# BMS_Master_V2_0.net
KiCad netlist of a schematic drawn in EAGLE
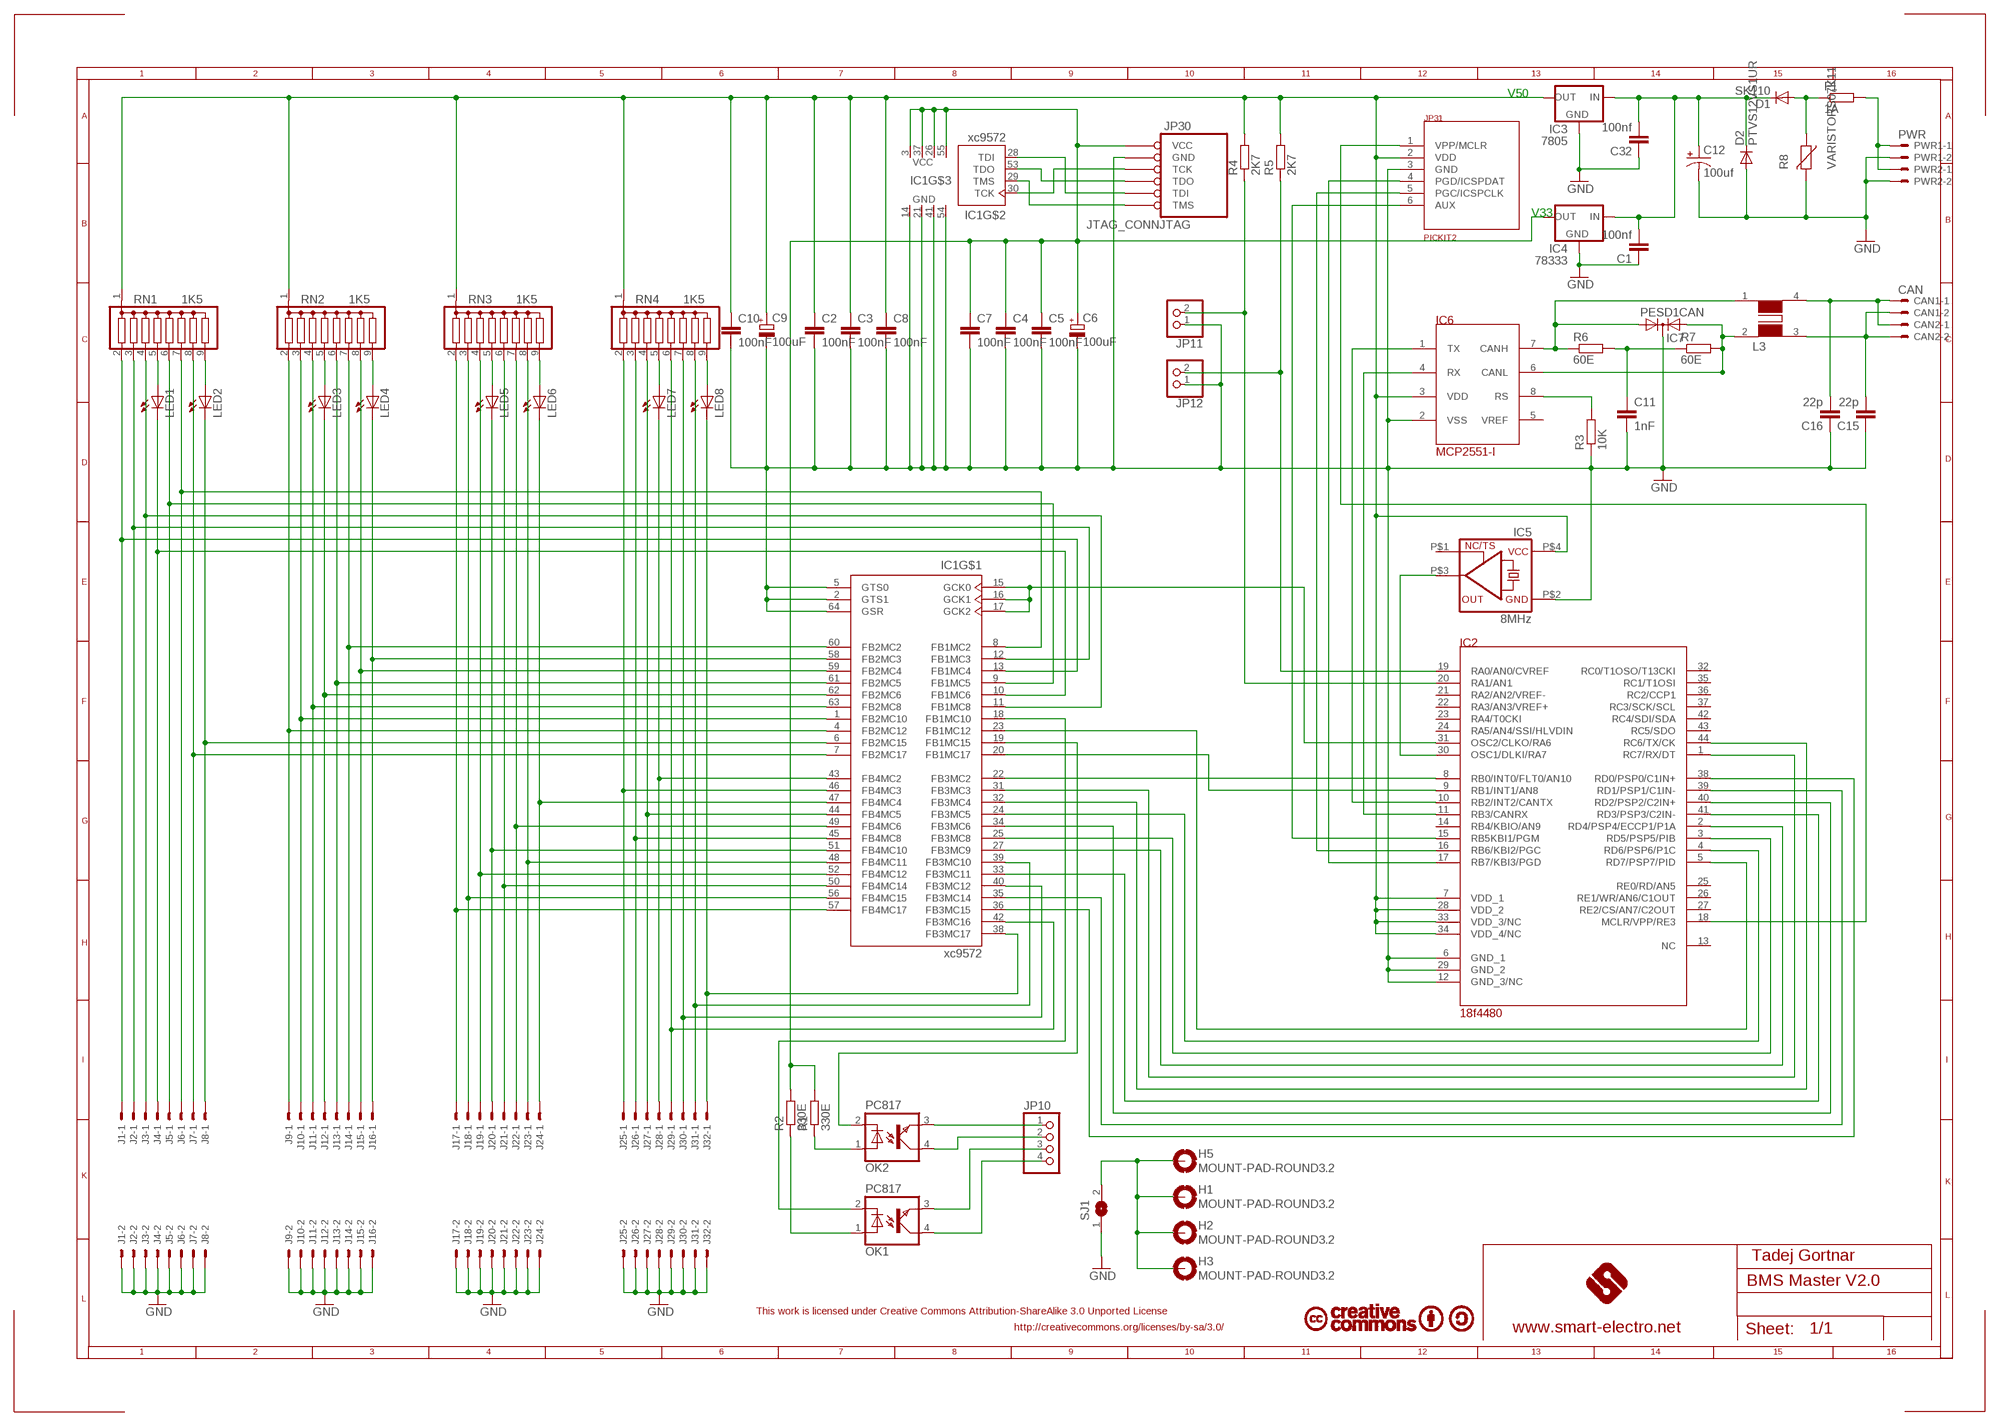
[diagram p0: schematic, sheet 1]

(export (version "E")
  (design (tool "Eeschema 10.0.6"))
  (components
    (comp (ref "C1")
      (value "100nf")
      (footprint "eagle-import:C0805")
      (libsource (lib "eagle-import") (part "resistor_C-EUC0805"))
    )
    (comp (ref "C2")
      (value "100nF")
      (footprint "eagle-import:C0805")
      (libsource (lib "eagle-import") (part "C-EUC0805"))
    )
    (comp (ref "C3")
      (value "100nF")
      (footprint "eagle-import:C0805")
      (libsource (lib "eagle-import") (part "C-EUC0805"))
    )
    (comp (ref "C4")
      (value "100nF")
      (footprint "eagle-import:C0805")
      (libsource (lib "eagle-import") (part "C-EUC0805"))
    )
    (comp (ref "C5")
      (value "100nF")
      (footprint "eagle-import:C0805")
      (libsource (lib "eagle-import") (part "C-EUC0805"))
    )
    (comp (ref "C6")
      (value "100uF")
      (footprint "eagle-import:E2,5-5")
      (libsource (lib "eagle-import") (part "CPOL-EUE2.5-5"))
    )
    (comp (ref "C7")
      (value "100nF")
      (footprint "eagle-import:C0805")
      (libsource (lib "eagle-import") (part "C-EUC0805"))
    )
    (comp (ref "C8")
      (value "100nF")
      (footprint "eagle-import:C0805")
      (libsource (lib "eagle-import") (part "C-EUC0805"))
    )
    (comp (ref "C9")
      (value "100uF")
      (footprint "eagle-import:E2,5-5")
      (libsource (lib "eagle-import") (part "CPOL-EUE2.5-5"))
    )
    (comp (ref "C10")
      (value "100nF")
      (footprint "eagle-import:C0805")
      (libsource (lib "eagle-import") (part "C-EUC0805"))
    )
    (comp (ref "C11")
      (value "1nF")
      (footprint "eagle-import:C0805")
      (libsource (lib "eagle-import") (part "C-EUC0805"))
    )
    (comp (ref "C12")
      (value "100uf")
      (footprint "eagle-import:PANASONIC_C")
      (libsource (lib "eagle-import") (part "CPOL-USC"))
    )
    (comp (ref "C15")
      (value "22p")
      (footprint "eagle-import:C0805")
      (libsource (lib "eagle-import") (part "C-EUC0805"))
    )
    (comp (ref "C16")
      (value "22p")
      (footprint "eagle-import:C0805")
      (libsource (lib "eagle-import") (part "C-EUC0805"))
    )
    (comp (ref "C32")
      (value "100nf")
      (footprint "eagle-import:C0805")
      (libsource (lib "eagle-import") (part "resistor_C-EUC0805"))
    )
    (comp (ref "CAN1")
      (value "CAN")
      (footprint "eagle-import:6410-02")
      (libsource (lib "eagle-import") (part "22-?-0227-2021"))
    )
    (comp (ref "CAN2")
      (value "CAN")
      (footprint "eagle-import:6410-02")
      (libsource (lib "eagle-import") (part "22-?-0227-2021"))
    )
    (comp (ref "D1")
      (value "SK110")
      (footprint "eagle-import:MINIMELF")
      (libsource (lib "eagle-import") (part "DIODE-MINIMELF"))
    )
    (comp (ref "D2")
      (value "PTVS12VS1UR")
      (footprint "eagle-import:SOD323-W")
      (libsource (lib "eagle-import") (part "DIODE-SOD323-W"))
    )
    (comp (ref "F1")
      (value "1A")
      (footprint "eagle-import:R1206")
      (libsource (lib "eagle-import") (part "resistor_R-EU_R1206"))
    )
    (comp (ref "H1")
      (value "MOUNT-PAD-ROUND3.2")
      (footprint "eagle-import:3,2-PAD")
      (libsource (lib "eagle-import") (part "MOUNT-PAD-ROUND3.2"))
    )
    (comp (ref "H2")
      (value "MOUNT-PAD-ROUND3.2")
      (footprint "eagle-import:3,2-PAD")
      (libsource (lib "eagle-import") (part "MOUNT-PAD-ROUND3.2"))
    )
    (comp (ref "H3")
      (value "MOUNT-PAD-ROUND3.2")
      (footprint "eagle-import:3,2-PAD")
      (libsource (lib "eagle-import") (part "MOUNT-PAD-ROUND3.2"))
    )
    (comp (ref "H5")
      (value "MOUNT-PAD-ROUND3.2")
      (footprint "eagle-import:3,2-PAD")
      (libsource (lib "eagle-import") (part "MOUNT-PAD-ROUND3.2"))
    )
    (comp (ref "IC1")
      (value "xc9572")
      (footprint "eagle-import:VQ64")
      (libsource (lib "eagle-import") (part "XC9572-VQ64"))
    )
    (comp (ref "IC2")
      (value "18f4480")
      (footprint "eagle-import:TQFP44")
      (libsource (lib "eagle-import") (part "PIC18F4804"))
    )
    (comp (ref "IC3")
      (value "7805")
      (footprint "eagle-import:SOT223")
      (libsource (lib "eagle-import") (part "78XXS'SOT223'"))
    )
    (comp (ref "IC4")
      (value "78333")
      (footprint "eagle-import:SOT223")
      (libsource (lib "eagle-import") (part "78XXS'SOT223'"))
    )
    (comp (ref "IC5")
      (value "8MHz")
      (footprint "eagle-import:CSX750")
      (libsource (lib "eagle-import") (part "OSCI7X5"))
    )
    (comp (ref "IC6")
      (value "MCP2551-I")
      (footprint "eagle-import:SO-08")
      (libsource (lib "eagle-import") (part "MCP2551"))
    )
    (comp (ref "IC7")
      (value "PESD1CAN")
      (footprint "eagle-import:SOT23")
      (libsource (lib "eagle-import") (part "BAS70-06"))
    )
    (comp (ref "J1")
      (value "22-27-2021-02")
      (footprint "eagle-import:6410-02")
      (libsource (lib "eagle-import") (part "22-?-0227-2021"))
    )
    (comp (ref "J2")
      (value "22-27-2021-02")
      (footprint "eagle-import:6410-02")
      (libsource (lib "eagle-import") (part "22-?-0227-2021"))
    )
    (comp (ref "J3")
      (value "22-27-2021-02")
      (footprint "eagle-import:6410-02")
      (libsource (lib "eagle-import") (part "22-?-0227-2021"))
    )
    (comp (ref "J4")
      (value "22-27-2021-02")
      (footprint "eagle-import:6410-02")
      (libsource (lib "eagle-import") (part "22-?-0227-2021"))
    )
    (comp (ref "J5")
      (value "22-27-2021-02")
      (footprint "eagle-import:6410-02")
      (libsource (lib "eagle-import") (part "22-?-0227-2021"))
    )
    (comp (ref "J6")
      (value "22-27-2021-02")
      (footprint "eagle-import:6410-02")
      (libsource (lib "eagle-import") (part "22-?-0227-2021"))
    )
    (comp (ref "J7")
      (value "22-27-2021-02")
      (footprint "eagle-import:6410-02")
      (libsource (lib "eagle-import") (part "22-?-0227-2021"))
    )
    (comp (ref "J8")
      (value "22-27-2021-02")
      (footprint "eagle-import:6410-02")
      (libsource (lib "eagle-import") (part "22-?-0227-2021"))
    )
    (comp (ref "J9")
      (value "22-27-2021-02")
      (footprint "eagle-import:6410-02")
      (libsource (lib "eagle-import") (part "22-?-0227-2021"))
    )
    (comp (ref "J10")
      (value "22-27-2021-02")
      (footprint "eagle-import:6410-02")
      (libsource (lib "eagle-import") (part "22-?-0227-2021"))
    )
    (comp (ref "J11")
      (value "22-27-2021-02")
      (footprint "eagle-import:6410-02")
      (libsource (lib "eagle-import") (part "22-?-0227-2021"))
    )
    (comp (ref "J12")
      (value "22-27-2021-02")
      (footprint "eagle-import:6410-02")
      (libsource (lib "eagle-import") (part "22-?-0227-2021"))
    )
    (comp (ref "J13")
      (value "22-27-2021-02")
      (footprint "eagle-import:6410-02")
      (libsource (lib "eagle-import") (part "22-?-0227-2021"))
    )
    (comp (ref "J14")
      (value "22-27-2021-02")
      (footprint "eagle-import:6410-02")
      (libsource (lib "eagle-import") (part "22-?-0227-2021"))
    )
    (comp (ref "J15")
      (value "22-27-2021-02")
      (footprint "eagle-import:6410-02")
      (libsource (lib "eagle-import") (part "22-?-0227-2021"))
    )
    (comp (ref "J16")
      (value "22-27-2021-02")
      (footprint "eagle-import:6410-02")
      (libsource (lib "eagle-import") (part "22-?-0227-2021"))
    )
    (comp (ref "J17")
      (value "22-27-2021-02")
      (footprint "eagle-import:6410-02")
      (libsource (lib "eagle-import") (part "22-?-0227-2021"))
    )
    (comp (ref "J18")
      (value "22-27-2021-02")
      (footprint "eagle-import:6410-02")
      (libsource (lib "eagle-import") (part "22-?-0227-2021"))
    )
    (comp (ref "J19")
      (value "22-27-2021-02")
      (footprint "eagle-import:6410-02")
      (libsource (lib "eagle-import") (part "22-?-0227-2021"))
    )
    (comp (ref "J20")
      (value "22-27-2021-02")
      (footprint "eagle-import:6410-02")
      (libsource (lib "eagle-import") (part "22-?-0227-2021"))
    )
    (comp (ref "J21")
      (value "22-27-2021-02")
      (footprint "eagle-import:6410-02")
      (libsource (lib "eagle-import") (part "22-?-0227-2021"))
    )
    (comp (ref "J22")
      (value "22-27-2021-02")
      (footprint "eagle-import:6410-02")
      (libsource (lib "eagle-import") (part "22-?-0227-2021"))
    )
    (comp (ref "J23")
      (value "22-27-2021-02")
      (footprint "eagle-import:6410-02")
      (libsource (lib "eagle-import") (part "22-?-0227-2021"))
    )
    (comp (ref "J24")
      (value "22-27-2021-02")
      (footprint "eagle-import:6410-02")
      (libsource (lib "eagle-import") (part "22-?-0227-2021"))
    )
    (comp (ref "J25")
      (value "22-27-2021-02")
      (footprint "eagle-import:6410-02")
      (libsource (lib "eagle-import") (part "22-?-0227-2021"))
    )
    (comp (ref "J26")
      (value "22-27-2021-02")
      (footprint "eagle-import:6410-02")
      (libsource (lib "eagle-import") (part "22-?-0227-2021"))
    )
    (comp (ref "J27")
      (value "22-27-2021-02")
      (footprint "eagle-import:6410-02")
      (libsource (lib "eagle-import") (part "22-?-0227-2021"))
    )
    (comp (ref "J28")
      (value "22-27-2021-02")
      (footprint "eagle-import:6410-02")
      (libsource (lib "eagle-import") (part "22-?-0227-2021"))
    )
    (comp (ref "J29")
      (value "22-27-2021-02")
      (footprint "eagle-import:6410-02")
      (libsource (lib "eagle-import") (part "22-?-0227-2021"))
    )
    (comp (ref "J30")
      (value "22-27-2021-02")
      (footprint "eagle-import:6410-02")
      (libsource (lib "eagle-import") (part "22-?-0227-2021"))
    )
    (comp (ref "J31")
      (value "22-27-2021-02")
      (footprint "eagle-import:6410-02")
      (libsource (lib "eagle-import") (part "22-?-0227-2021"))
    )
    (comp (ref "J32")
      (value "22-27-2021-02")
      (footprint "eagle-import:6410-02")
      (libsource (lib "eagle-import") (part "22-?-0227-2021"))
    )
    (comp (ref "JP10")
      (value "PINHD-1X4")
      (footprint "eagle-import:1X04")
      (libsource (lib "eagle-import") (part "PINHD-1X4"))
    )
    (comp (ref "JP11")
      (value "PINHD-1X2")
      (footprint "eagle-import:1X02")
      (libsource (lib "eagle-import") (part "PINHD-1X2"))
    )
    (comp (ref "JP12")
      (value "PINHD-1X2")
      (footprint "eagle-import:1X02")
      (libsource (lib "eagle-import") (part "PINHD-1X2"))
    )
    (comp (ref "JP30")
      (value "JTAG_CONNJTAG")
      (footprint "eagle-import:PIN06")
      (libsource (lib "eagle-import") (part "JTAG_CONNJTAG"))
    )
    (comp (ref "JP31")
      (value "PICKIT2")
      (footprint "eagle-import:PINHD-1X6")
      (libsource (lib "eagle-import") (part "PICKIT2"))
    )
    (comp (ref "L3")
      (value "WE-DD_M/S")
      (footprint "eagle-import:WE-DD_M_S")
      (libsource (lib "eagle-import") (part "WE-DD_M/S"))
    )
    (comp (ref "LED1")
      (value "LEDCHIPLED_0805")
      (footprint "eagle-import:CHIPLED_0805")
      (libsource (lib "eagle-import") (part "LEDCHIPLED_0805"))
    )
    (comp (ref "LED2")
      (value "LEDCHIPLED_0805")
      (footprint "eagle-import:CHIPLED_0805")
      (libsource (lib "eagle-import") (part "LEDCHIPLED_0805"))
    )
    (comp (ref "LED3")
      (value "LEDCHIPLED_0805")
      (footprint "eagle-import:CHIPLED_0805")
      (libsource (lib "eagle-import") (part "LEDCHIPLED_0805"))
    )
    (comp (ref "LED4")
      (value "LEDCHIPLED_0805")
      (footprint "eagle-import:CHIPLED_0805")
      (libsource (lib "eagle-import") (part "LEDCHIPLED_0805"))
    )
    (comp (ref "LED5")
      (value "LEDCHIPLED_0805")
      (footprint "eagle-import:CHIPLED_0805")
      (libsource (lib "eagle-import") (part "LEDCHIPLED_0805"))
    )
    (comp (ref "LED6")
      (value "LEDCHIPLED_0805")
      (footprint "eagle-import:CHIPLED_0805")
      (libsource (lib "eagle-import") (part "LEDCHIPLED_0805"))
    )
    (comp (ref "LED7")
      (value "LEDCHIPLED_0805")
      (footprint "eagle-import:CHIPLED_0805")
      (libsource (lib "eagle-import") (part "LEDCHIPLED_0805"))
    )
    (comp (ref "LED8")
      (value "LEDCHIPLED_0805")
      (footprint "eagle-import:CHIPLED_0805")
      (libsource (lib "eagle-import") (part "LEDCHIPLED_0805"))
    )
    (comp (ref "OK1")
      (value "PC817")
      (footprint "eagle-import:DIL04")
      (libsource (lib "eagle-import") (part "PC817"))
    )
    (comp (ref "OK2")
      (value "PC817")
      (footprint "eagle-import:DIL04")
      (libsource (lib "eagle-import") (part "PC817"))
    )
    (comp (ref "PWR1")
      (value "PWR")
      (footprint "eagle-import:6410-02")
      (libsource (lib "eagle-import") (part "22-?-0227-2021"))
    )
    (comp (ref "PWR2")
      (value "PWR")
      (footprint "eagle-import:6410-02")
      (libsource (lib "eagle-import") (part "22-?-0227-2021"))
    )
    (comp (ref "R1")
      (value "330E")
      (footprint "eagle-import:M0805")
      (libsource (lib "eagle-import") (part "R-EU_M0805"))
    )
    (comp (ref "R2")
      (value "330E")
      (footprint "eagle-import:M0805")
      (libsource (lib "eagle-import") (part "R-EU_M0805"))
    )
    (comp (ref "R3")
      (value "10K")
      (footprint "eagle-import:M0805")
      (libsource (lib "eagle-import") (part "R-EU_M0805"))
    )
    (comp (ref "R4")
      (value "2K7")
      (footprint "eagle-import:M0805")
      (libsource (lib "eagle-import") (part "R-EU_M0805"))
    )
    (comp (ref "R5")
      (value "2K7")
      (footprint "eagle-import:M0805")
      (libsource (lib "eagle-import") (part "R-EU_M0805"))
    )
    (comp (ref "R6")
      (value "60E")
      (footprint "eagle-import:R0805")
      (libsource (lib "eagle-import") (part "R-EU_R0805"))
    )
    (comp (ref "R7")
      (value "60E")
      (footprint "eagle-import:R0805")
      (libsource (lib "eagle-import") (part "R-EU_R0805"))
    )
    (comp (ref "R8")
      (value "VARISTORS07K11")
      (footprint "eagle-import:S07K11")
      (libsource (lib "eagle-import") (part "VARISTORS07K11"))
    )
    (comp (ref "RN1")
      (value "1K5")
      (footprint "eagle-import:SIL9")
      (libsource (lib "eagle-import") (part "G08R"))
    )
    (comp (ref "RN2")
      (value "1K5")
      (footprint "eagle-import:SIL9")
      (libsource (lib "eagle-import") (part "G08R"))
    )
    (comp (ref "RN3")
      (value "1K5")
      (footprint "eagle-import:SIL9")
      (libsource (lib "eagle-import") (part "G08R"))
    )
    (comp (ref "RN4")
      (value "1K5")
      (footprint "eagle-import:SIL9")
      (libsource (lib "eagle-import") (part "G08R"))
    )
    (comp (ref "SJ1") (value "SJ") (footprint "eagle-import:SJ") (libsource (lib "eagle-import") (part "SJ")))
  )
  (nets
    (net (code "1") (name "/V33") (class "Default")
      (node (ref "C4") (pin "1") (pinfunction "1_1") (pintype "passive"))
      (node (ref "C5") (pin "1") (pinfunction "1_1") (pintype "passive"))
      (node (ref "C6") (pin "+") (pinfunction "+_+") (pintype "passive"))
      (node (ref "C7") (pin "1") (pinfunction "1_1") (pintype "passive"))
      (node (ref "IC1") (pin "26") (pinfunction "VCC_26") (pintype "power_in"))
      (node (ref "IC1") (pin "3") (pinfunction "VCC_3") (pintype "power_in"))
      (node (ref "IC1") (pin "37") (pinfunction "VCC_37") (pintype "power_in"))
      (node (ref "IC1") (pin "55") (pinfunction "VCC_55") (pintype "power_in"))
      (node (ref "IC4") (pin "3") (pinfunction "OUT_3") (pintype "passive"))
      (node (ref "JP30") (pin "1") (pinfunction "VCC_1") (pintype "passive"))
      (node (ref "R1") (pin "2") (pinfunction "2_2") (pintype "passive"))
      (node (ref "R2") (pin "2") (pinfunction "2_2") (pintype "passive"))
    )
    (net (code "2") (name "/V50") (class "Default")
      (node (ref "C10") (pin "1") (pinfunction "1_1") (pintype "passive"))
      (node (ref "C2") (pin "1") (pinfunction "1_1") (pintype "passive"))
      (node (ref "C3") (pin "1") (pinfunction "1_1") (pintype "passive"))
      (node (ref "C8") (pin "1") (pinfunction "1_1") (pintype "passive"))
      (node (ref "C9") (pin "+") (pinfunction "+_+") (pintype "passive"))
      (node (ref "IC2") (pin "28") (pinfunction "VDD_2_28") (pintype "power_in"))
      (node (ref "IC2") (pin "33") (pinfunction "VDD_3/NC_33") (pintype "power_in"))
      (node (ref "IC2") (pin "34") (pinfunction "VDD_4/NC_34") (pintype "power_in"))
      (node (ref "IC2") (pin "7") (pinfunction "VDD_1_7") (pintype "power_in"))
      (node (ref "IC3") (pin "3") (pinfunction "OUT_3") (pintype "passive"))
      (node (ref "IC5") (pin "P$4") (pinfunction "VCC_P$4") (pintype "power_in"))
      (node (ref "IC6") (pin "3") (pinfunction "VDD_3") (pintype "power_in"))
      (node (ref "JP31") (pin "2") (pinfunction "VDD_2") (pintype "bidirectional"))
      (node (ref "R4") (pin "2") (pinfunction "2_2") (pintype "passive"))
      (node (ref "R5") (pin "2") (pinfunction "2_2") (pintype "passive"))
      (node (ref "RN1") (pin "1") (pinfunction "1_1") (pintype "passive"))
      (node (ref "RN2") (pin "1") (pinfunction "1_1") (pintype "passive"))
      (node (ref "RN3") (pin "1") (pinfunction "1_1") (pintype "passive"))
      (node (ref "RN4") (pin "1") (pinfunction "1_1") (pintype "passive"))
    )
    (net (code "3") (name "GND") (class "Default")
      (node (ref "C1") (pin "1") (pinfunction "1_1") (pintype "passive"))
      (node (ref "C10") (pin "2") (pinfunction "2_2") (pintype "passive"))
      (node (ref "C11") (pin "2") (pinfunction "2_2") (pintype "passive"))
      (node (ref "C12") (pin "-") (pinfunction "-_-") (pintype "passive"))
      (node (ref "C15") (pin "1") (pinfunction "1_1") (pintype "passive"))
      (node (ref "C16") (pin "1") (pinfunction "1_1") (pintype "passive"))
      (node (ref "C2") (pin "2") (pinfunction "2_2") (pintype "passive"))
      (node (ref "C3") (pin "2") (pinfunction "2_2") (pintype "passive"))
      (node (ref "C32") (pin "1") (pinfunction "1_1") (pintype "passive"))
      (node (ref "C4") (pin "2") (pinfunction "2_2") (pintype "passive"))
      (node (ref "C5") (pin "2") (pinfunction "2_2") (pintype "passive"))
      (node (ref "C6") (pin "-") (pinfunction "-_-") (pintype "passive"))
      (node (ref "C7") (pin "2") (pinfunction "2_2") (pintype "passive"))
      (node (ref "C8") (pin "2") (pinfunction "2_2") (pintype "passive"))
      (node (ref "C9") (pin "-") (pinfunction "-_-") (pintype "passive"))
      (node (ref "D2") (pin "A") (pinfunction "A_A") (pintype "passive"))
      (node (ref "IC1") (pin "14") (pinfunction "GND_14") (pintype "power_in"))
      (node (ref "IC1") (pin "2") (pinfunction "GTS1_2") (pintype "input"))
      (node (ref "IC1") (pin "21") (pinfunction "GND_21") (pintype "power_in"))
      (node (ref "IC1") (pin "41") (pinfunction "GND_41") (pintype "power_in"))
      (node (ref "IC1") (pin "5") (pinfunction "GTS0_5") (pintype "input"))
      (node (ref "IC1") (pin "54") (pinfunction "GND_54") (pintype "power_in"))
      (node (ref "IC1") (pin "64") (pinfunction "GSR_64") (pintype "input"))
      (node (ref "IC2") (pin "12") (pinfunction "GND_3/NC_12") (pintype "power_in"))
      (node (ref "IC2") (pin "29") (pinfunction "GND_2_29") (pintype "power_in"))
      (node (ref "IC2") (pin "6") (pinfunction "GND_1_6") (pintype "power_in"))
      (node (ref "IC3") (pin "2") (pinfunction "GND_2") (pintype "input"))
      (node (ref "IC4") (pin "2") (pinfunction "GND_2") (pintype "input"))
      (node (ref "IC5") (pin "P$2") (pinfunction "GND_P$2") (pintype "power_in"))
      (node (ref "IC6") (pin "2") (pinfunction "VSS_2") (pintype "power_in"))
      (node (ref "IC7") (pin "3") (pinfunction "C_3") (pintype "passive"))
      (node (ref "J1") (pin "2") (pinfunction "S_2") (pintype "passive"))
      (node (ref "J10") (pin "2") (pinfunction "S_2") (pintype "passive"))
      (node (ref "J11") (pin "2") (pinfunction "S_2") (pintype "passive"))
      (node (ref "J12") (pin "2") (pinfunction "S_2") (pintype "passive"))
      (node (ref "J13") (pin "2") (pinfunction "S_2") (pintype "passive"))
      (node (ref "J14") (pin "2") (pinfunction "S_2") (pintype "passive"))
      (node (ref "J15") (pin "2") (pinfunction "S_2") (pintype "passive"))
      (node (ref "J16") (pin "2") (pinfunction "S_2") (pintype "passive"))
      (node (ref "J17") (pin "2") (pinfunction "S_2") (pintype "passive"))
      (node (ref "J18") (pin "2") (pinfunction "S_2") (pintype "passive"))
      (node (ref "J19") (pin "2") (pinfunction "S_2") (pintype "passive"))
      (node (ref "J2") (pin "2") (pinfunction "S_2") (pintype "passive"))
      (node (ref "J20") (pin "2") (pinfunction "S_2") (pintype "passive"))
      (node (ref "J21") (pin "2") (pinfunction "S_2") (pintype "passive"))
      (node (ref "J22") (pin "2") (pinfunction "S_2") (pintype "passive"))
      (node (ref "J23") (pin "2") (pinfunction "S_2") (pintype "passive"))
      (node (ref "J24") (pin "2") (pinfunction "S_2") (pintype "passive"))
      (node (ref "J25") (pin "2") (pinfunction "S_2") (pintype "passive"))
      (node (ref "J26") (pin "2") (pinfunction "S_2") (pintype "passive"))
      (node (ref "J27") (pin "2") (pinfunction "S_2") (pintype "passive"))
      (node (ref "J28") (pin "2") (pinfunction "S_2") (pintype "passive"))
      (node (ref "J29") (pin "2") (pinfunction "S_2") (pintype "passive"))
      (node (ref "J3") (pin "2") (pinfunction "S_2") (pintype "passive"))
      (node (ref "J30") (pin "2") (pinfunction "S_2") (pintype "passive"))
      (node (ref "J31") (pin "2") (pinfunction "S_2") (pintype "passive"))
      (node (ref "J32") (pin "2") (pinfunction "S_2") (pintype "passive"))
      (node (ref "J4") (pin "2") (pinfunction "S_2") (pintype "passive"))
      (node (ref "J5") (pin "2") (pinfunction "S_2") (pintype "passive"))
      (node (ref "J6") (pin "2") (pinfunction "S_2") (pintype "passive"))
      (node (ref "J7") (pin "2") (pinfunction "S_2") (pintype "passive"))
      (node (ref "J8") (pin "2") (pinfunction "S_2") (pintype "passive"))
      (node (ref "J9") (pin "2") (pinfunction "S_2") (pintype "passive"))
      (node (ref "JP11") (pin "1") (pinfunction "1_1") (pintype "passive"))
      (node (ref "JP12") (pin "1") (pinfunction "1_1") (pintype "passive"))
      (node (ref "JP30") (pin "2") (pinfunction "GND_2") (pintype "passive"))
      (node (ref "JP31") (pin "3") (pinfunction "GND_3") (pintype "bidirectional"))
      (node (ref "PWR1") (pin "2") (pinfunction "S_2") (pintype "passive"))
      (node (ref "PWR2") (pin "2") (pinfunction "S_2") (pintype "passive"))
      (node (ref "R3") (pin "1") (pinfunction "1_1") (pintype "passive"))
      (node (ref "R8") (pin "2") (pinfunction "2_2") (pintype "passive"))
      (node (ref "SJ1") (pin "1") (pinfunction "1_1") (pintype "passive"))
    )
    (net (code "4") (name "Net-(C11-Pad1)") (class "Default")
      (node (ref "C11") (pin "1") (pinfunction "1_1") (pintype "passive"))
      (node (ref "R6") (pin "2") (pinfunction "2_2") (pintype "passive"))
      (node (ref "R7") (pin "1") (pinfunction "1_1") (pintype "passive"))
    )
    (net (code "5") (name "Net-(CAN1A-S)") (class "Default")
      (node (ref "C16") (pin "2") (pinfunction "2_2") (pintype "passive"))
      (node (ref "CAN1") (pin "1") (pinfunction "S_1") (pintype "passive"))
      (node (ref "CAN2") (pin "1") (pinfunction "S_1") (pintype "passive"))
      (node (ref "L3") (pin "4") (pinfunction "3_4") (pintype "passive"))
    )
    (net (code "6") (name "Net-(CAN1B-S)") (class "Default")
      (node (ref "C15") (pin "2") (pinfunction "2_2") (pintype "passive"))
      (node (ref "CAN1") (pin "2") (pinfunction "S_2") (pintype "passive"))
      (node (ref "CAN2") (pin "2") (pinfunction "S_2") (pintype "passive"))
      (node (ref "L3") (pin "3") (pinfunction "4_3") (pintype "passive"))
    )
    (net (code "7") (name "Net-(D1-PadA)") (class "Default")
      (node (ref "D1") (pin "A") (pinfunction "A_A") (pintype "passive"))
      (node (ref "F1") (pin "1") (pinfunction "1_1") (pintype "passive"))
      (node (ref "R8") (pin "1") (pinfunction "1_1") (pintype "passive"))
    )
    (net (code "8") (name "Net-(H1-MOUNT)") (class "Default")
      (node (ref "H1") (pin "B3,2") (pinfunction "MOUNT_B3,2") (pintype "passive"))
      (node (ref "H2") (pin "B3,2") (pinfunction "MOUNT_B3,2") (pintype "passive"))
      (node (ref "H3") (pin "B3,2") (pinfunction "MOUNT_B3,2") (pintype "passive"))
      (node (ref "H5") (pin "B3,2") (pinfunction "MOUNT_B3,2") (pintype "passive"))
      (node (ref "SJ1") (pin "2") (pinfunction "2_2") (pintype "passive"))
    )
    (net (code "9") (name "Net-(IC1A-FB1MC2)") (class "Default")
      (node (ref "IC1") (pin "8") (pinfunction "FB1MC2_8") (pintype "bidirectional"))
      (node (ref "J6") (pin "1") (pinfunction "S_1") (pintype "passive"))
      (node (ref "RN1") (pin "7") (pinfunction "7_7") (pintype "passive"))
    )
    (net (code "10") (name "Net-(IC1A-FB1MC3)") (class "Default")
      (node (ref "IC1") (pin "12") (pinfunction "FB1MC3_12") (pintype "bidirectional"))
      (node (ref "J2") (pin "1") (pinfunction "S_1") (pintype "passive"))
      (node (ref "RN1") (pin "3") (pinfunction "3_3") (pintype "passive"))
    )
    (net (code "11") (name "Net-(IC1A-FB1MC4)") (class "Default")
      (node (ref "IC1") (pin "13") (pinfunction "FB1MC4_13") (pintype "bidirectional"))
      (node (ref "J1") (pin "1") (pinfunction "S_1") (pintype "passive"))
      (node (ref "RN1") (pin "2") (pinfunction "2_2") (pintype "passive"))
    )
    (net (code "12") (name "Net-(IC1A-FB1MC5)") (class "Default")
      (node (ref "IC1") (pin "9") (pinfunction "FB1MC5_9") (pintype "bidirectional"))
      (node (ref "J5") (pin "1") (pinfunction "S_1") (pintype "passive"))
      (node (ref "RN1") (pin "6") (pinfunction "6_6") (pintype "passive"))
    )
    (net (code "13") (name "Net-(IC1A-FB1MC6)") (class "Default")
      (node (ref "IC1") (pin "10") (pinfunction "FB1MC6_10") (pintype "bidirectional"))
      (node (ref "J4") (pin "1") (pinfunction "S_1") (pintype "passive"))
      (node (ref "LED1") (pin "C") (pinfunction "C_C") (pintype "passive"))
    )
    (net (code "14") (name "Net-(IC1A-FB1MC8)") (class "Default")
      (node (ref "IC1") (pin "11") (pinfunction "FB1MC8_11") (pintype "bidirectional"))
      (node (ref "J3") (pin "1") (pinfunction "S_1") (pintype "passive"))
      (node (ref "RN1") (pin "4") (pinfunction "4_4") (pintype "passive"))
    )
    (net (code "15") (name "Net-(IC1A-FB1MC10)") (class "Default")
      (node (ref "IC1") (pin "18") (pinfunction "FB1MC10_18") (pintype "bidirectional"))
      (node (ref "OK1") (pin "2") (pinfunction "C_2") (pintype "passive"))
    )
    (net (code "16") (name "Net-(IC1A-FB1MC12)") (class "Default")
      (node (ref "IC1") (pin "23") (pinfunction "FB1MC12_23") (pintype "bidirectional"))
      (node (ref "IC2") (pin "5") (pinfunction "RD7/PSP7/PID_5") (pintype "bidirectional"))
    )
    (net (code "17") (name "Net-(IC1A-FB1MC15)") (class "Default")
      (node (ref "IC1") (pin "19") (pinfunction "FB1MC15_19") (pintype "bidirectional"))
      (node (ref "OK2") (pin "2") (pinfunction "C_2") (pintype "passive"))
    )
    (net (code "18") (name "Net-(IC1A-FB1MC17)") (class "Default")
      (node (ref "IC1") (pin "20") (pinfunction "FB1MC17_20") (pintype "bidirectional"))
      (node (ref "IC2") (pin "9") (pinfunction "RB1/INT1/AN8_9") (pintype "bidirectional"))
    )
    (net (code "19") (name "Net-(IC1A-FB2MC2)") (class "Default")
      (node (ref "IC1") (pin "60") (pinfunction "FB2MC2_60") (pintype "bidirectional"))
      (node (ref "J14") (pin "1") (pinfunction "S_1") (pintype "passive"))
      (node (ref "RN2") (pin "7") (pinfunction "7_7") (pintype "passive"))
    )
    (net (code "20") (name "Net-(IC1A-FB2MC3)") (class "Default")
      (node (ref "IC1") (pin "58") (pinfunction "FB2MC3_58") (pintype "bidirectional"))
      (node (ref "J16") (pin "1") (pinfunction "S_1") (pintype "passive"))
      (node (ref "LED4") (pin "C") (pinfunction "C_C") (pintype "passive"))
    )
    (net (code "21") (name "Net-(IC1A-FB2MC4)") (class "Default")
      (node (ref "IC1") (pin "59") (pinfunction "FB2MC4_59") (pintype "bidirectional"))
      (node (ref "J15") (pin "1") (pinfunction "S_1") (pintype "passive"))
      (node (ref "RN2") (pin "8") (pinfunction "8_8") (pintype "passive"))
    )
    (net (code "22") (name "Net-(IC1A-FB2MC5)") (class "Default")
      (node (ref "IC1") (pin "61") (pinfunction "FB2MC5_61") (pintype "bidirectional"))
      (node (ref "J13") (pin "1") (pinfunction "S_1") (pintype "passive"))
      (node (ref "RN2") (pin "6") (pinfunction "6_6") (pintype "passive"))
    )
    (net (code "23") (name "Net-(IC1A-FB2MC6)") (class "Default")
      (node (ref "IC1") (pin "62") (pinfunction "FB2MC6_62") (pintype "bidirectional"))
      (node (ref "J12") (pin "1") (pinfunction "S_1") (pintype "passive"))
      (node (ref "LED3") (pin "C") (pinfunction "C_C") (pintype "passive"))
    )
    (net (code "24") (name "Net-(IC1A-FB2MC8)") (class "Default")
      (node (ref "IC1") (pin "63") (pinfunction "FB2MC8_63") (pintype "bidirectional"))
      (node (ref "J11") (pin "1") (pinfunction "S_1") (pintype "passive"))
      (node (ref "RN2") (pin "4") (pinfunction "4_4") (pintype "passive"))
    )
    (net (code "25") (name "Net-(IC1A-FB2MC10)") (class "Default")
      (node (ref "IC1") (pin "1") (pinfunction "FB2MC10_1") (pintype "bidirectional"))
      (node (ref "J10") (pin "1") (pinfunction "S_1") (pintype "passive"))
      (node (ref "RN2") (pin "3") (pinfunction "3_3") (pintype "passive"))
    )
    (net (code "26") (name "Net-(IC1A-FB2MC12)") (class "Default")
      (node (ref "IC1") (pin "4") (pinfunction "FB2MC12_4") (pintype "bidirectional"))
      (node (ref "J9") (pin "1") (pinfunction "S_1") (pintype "passive"))
      (node (ref "RN2") (pin "2") (pinfunction "2_2") (pintype "passive"))
    )
    (net (code "27") (name "Net-(IC1A-FB2MC15)") (class "Default")
      (node (ref "IC1") (pin "6") (pinfunction "FB2MC15_6") (pintype "bidirectional"))
      (node (ref "J8") (pin "1") (pinfunction "S_1") (pintype "passive"))
      (node (ref "LED2") (pin "C") (pinfunction "C_C") (pintype "passive"))
    )
    (net (code "28") (name "Net-(IC1A-FB2MC17)") (class "Default")
      (node (ref "IC1") (pin "7") (pinfunction "FB2MC17_7") (pintype "bidirectional"))
      (node (ref "J7") (pin "1") (pinfunction "S_1") (pintype "passive"))
      (node (ref "RN1") (pin "8") (pinfunction "8_8") (pintype "passive"))
    )
    (net (code "29") (name "Net-(IC1A-FB3MC2)") (class "Default")
      (node (ref "IC1") (pin "22") (pinfunction "FB3MC2_22") (pintype "bidirectional"))
      (node (ref "IC2") (pin "8") (pinfunction "RB0/INT0/FLT0/AN10_8") (pintype "bidirectional"))
    )
    (net (code "30") (name "Net-(IC1A-FB3MC3)") (class "Default")
      (node (ref "IC1") (pin "31") (pinfunction "FB3MC3_31") (pintype "bidirectional"))
      (node (ref "IC2") (pin "1") (pinfunction "RC7/RX/DT_1") (pintype "bidirectional"))
    )
    (net (code "31") (name "Net-(IC1A-FB3MC4)") (class "Default")
      (node (ref "IC1") (pin "32") (pinfunction "FB3MC4_32") (pintype "bidirectional"))
      (node (ref "IC2") (pin "44") (pinfunction "RC6/TX/CK_44") (pintype "bidirectional"))
    )
    (net (code "32") (name "Net-(IC1A-FB3MC5)") (class "Default")
      (node (ref "IC1") (pin "24") (pinfunction "FB3MC5_24") (pintype "bidirectional"))
      (node (ref "IC2") (pin "4") (pinfunction "RD6/PSP6/P1C_4") (pintype "bidirectional"))
    )
    (net (code "33") (name "Net-(IC1A-FB3MC6)") (class "Default")
      (node (ref "IC1") (pin "34") (pinfunction "FB3MC6_34") (pintype "bidirectional"))
      (node (ref "IC2") (pin "40") (pinfunction "RD2/PSP2/C2IN+_40") (pintype "bidirectional"))
    )
    (net (code "34") (name "Net-(IC1A-FB3MC8)") (class "Default")
      (node (ref "IC1") (pin "25") (pinfunction "FB3MC8_25") (pintype "bidirectional"))
      (node (ref "IC2") (pin "3") (pinfunction "RD5/PSP5/PIB_3") (pintype "bidirectional"))
    )
    (net (code "35") (name "Net-(IC1A-FB3MC9)") (class "Default")
      (node (ref "IC1") (pin "27") (pinfunction "FB3MC9_27") (pintype "bidirectional"))
      (node (ref "IC2") (pin "2") (pinfunction "RD4/PSP4/ECCP1/P1A_2") (pintype "bidirectional"))
    )
    (net (code "36") (name "Net-(IC1A-FB3MC10)") (class "Default")
      (node (ref "IC1") (pin "39") (pinfunction "FB3MC10_39") (pintype "bidirectional"))
      (node (ref "J31") (pin "1") (pinfunction "S_1") (pintype "passive"))
      (node (ref "RN4") (pin "8") (pinfunction "8_8") (pintype "passive"))
    )
    (net (code "37") (name "Net-(IC1A-FB3MC11)") (class "Default")
      (node (ref "IC1") (pin "33") (pinfunction "FB3MC11_33") (pintype "bidirectional"))
      (node (ref "IC2") (pin "41") (pinfunction "RD3/PSP3/C2IN-_41") (pintype "bidirectional"))
    )
    (net (code "38") (name "Net-(IC1A-FB3MC12)") (class "Default")
      (node (ref "IC1") (pin "40") (pinfunction "FB3MC12_40") (pintype "bidirectional"))
      (node (ref "J30") (pin "1") (pinfunction "S_1") (pintype "passive"))
      (node (ref "RN4") (pin "7") (pinfunction "7_7") (pintype "passive"))
    )
    (net (code "39") (name "Net-(IC1A-FB3MC14)") (class "Default")
      (node (ref "IC1") (pin "35") (pinfunction "FB3MC14_35") (pintype "bidirectional"))
      (node (ref "IC2") (pin "39") (pinfunction "RD1/PSP1/C1IN-_39") (pintype "bidirectional"))
    )
    (net (code "40") (name "Net-(IC1A-FB3MC15)") (class "Default")
      (node (ref "IC1") (pin "36") (pinfunction "FB3MC15_36") (pintype "bidirectional"))
      (node (ref "IC2") (pin "38") (pinfunction "RD0/PSP0/C1IN+_38") (pintype "bidirectional"))
    )
    (net (code "41") (name "Net-(IC1A-FB3MC16)") (class "Default")
      (node (ref "IC1") (pin "42") (pinfunction "FB3MC16_42") (pintype "bidirectional"))
      (node (ref "J29") (pin "1") (pinfunction "S_1") (pintype "passive"))
      (node (ref "RN4") (pin "6") (pinfunction "6_6") (pintype "passive"))
    )
    (net (code "42") (name "Net-(IC1A-FB3MC17)") (class "Default")
      (node (ref "IC1") (pin "38") (pinfunction "FB3MC17_38") (pintype "bidirectional"))
      (node (ref "J32") (pin "1") (pinfunction "S_1") (pintype "passive"))
      (node (ref "LED8") (pin "C") (pinfunction "C_C") (pintype "passive"))
    )
    (net (code "43") (name "Net-(IC1A-FB4MC2)") (class "Default")
      (node (ref "IC1") (pin "43") (pinfunction "FB4MC2_43") (pintype "bidirectional"))
      (node (ref "J28") (pin "1") (pinfunction "S_1") (pintype "passive"))
      (node (ref "LED7") (pin "C") (pinfunction "C_C") (pintype "passive"))
    )
    (net (code "44") (name "Net-(IC1A-FB4MC3)") (class "Default")
      (node (ref "IC1") (pin "46") (pinfunction "FB4MC3_46") (pintype "bidirectional"))
      (node (ref "J25") (pin "1") (pinfunction "S_1") (pintype "passive"))
      (node (ref "RN4") (pin "2") (pinfunction "2_2") (pintype "passive"))
    )
    (net (code "45") (name "Net-(IC1A-FB4MC4)") (class "Default")
      (node (ref "IC1") (pin "47") (pinfunction "FB4MC4_47") (pintype "bidirectional"))
      (node (ref "J24") (pin "1") (pinfunction "S_1") (pintype "passive"))
      (node (ref "LED6") (pin "C") (pinfunction "C_C") (pintype "passive"))
    )
    (net (code "46") (name "Net-(IC1A-FB4MC5)") (class "Default")
      (node (ref "IC1") (pin "44") (pinfunction "FB4MC5_44") (pintype "bidirectional"))
      (node (ref "J27") (pin "1") (pinfunction "S_1") (pintype "passive"))
      (node (ref "RN4") (pin "4") (pinfunction "4_4") (pintype "passive"))
    )
    (net (code "47") (name "Net-(IC1A-FB4MC6)") (class "Default")
      (node (ref "IC1") (pin "49") (pinfunction "FB4MC6_49") (pintype "bidirectional"))
      (node (ref "J22") (pin "1") (pinfunction "S_1") (pintype "passive"))
      (node (ref "RN3") (pin "7") (pinfunction "7_7") (pintype "passive"))
    )
    (net (code "48") (name "Net-(IC1A-FB4MC8)") (class "Default")
      (node (ref "IC1") (pin "45") (pinfunction "FB4MC8_45") (pintype "bidirectional"))
      (node (ref "J26") (pin "1") (pinfunction "S_1") (pintype "passive"))
      (node (ref "RN4") (pin "3") (pinfunction "3_3") (pintype "passive"))
    )
    (net (code "49") (name "Net-(IC1A-FB4MC10)") (class "Default")
      (node (ref "IC1") (pin "51") (pinfunction "FB4MC10_51") (pintype "bidirectional"))
      (node (ref "J20") (pin "1") (pinfunction "S_1") (pintype "passive"))
      (node (ref "LED5") (pin "C") (pinfunction "C_C") (pintype "passive"))
    )
    (net (code "50") (name "Net-(IC1A-FB4MC11)") (class "Default")
      (node (ref "IC1") (pin "48") (pinfunction "FB4MC11_48") (pintype "bidirectional"))
      (node (ref "J23") (pin "1") (pinfunction "S_1") (pintype "passive"))
      (node (ref "RN3") (pin "8") (pinfunction "8_8") (pintype "passive"))
    )
    (net (code "51") (name "Net-(IC1A-FB4MC12)") (class "Default")
      (node (ref "IC1") (pin "52") (pinfunction "FB4MC12_52") (pintype "bidirectional"))
      (node (ref "J19") (pin "1") (pinfunction "S_1") (pintype "passive"))
      (node (ref "RN3") (pin "4") (pinfunction "4_4") (pintype "passive"))
    )
    (net (code "52") (name "Net-(IC1A-FB4MC14)") (class "Default")
      (node (ref "IC1") (pin "50") (pinfunction "FB4MC14_50") (pintype "bidirectional"))
      (node (ref "J21") (pin "1") (pinfunction "S_1") (pintype "passive"))
      (node (ref "RN3") (pin "6") (pinfunction "6_6") (pintype "passive"))
    )
    (net (code "53") (name "Net-(IC1A-FB4MC15)") (class "Default")
      (node (ref "IC1") (pin "56") (pinfunction "FB4MC15_56") (pintype "bidirectional"))
      (node (ref "J18") (pin "1") (pinfunction "S_1") (pintype "passive"))
      (node (ref "RN3") (pin "3") (pinfunction "3_3") (pintype "passive"))
    )
    (net (code "54") (name "Net-(IC1A-FB4MC17)") (class "Default")
      (node (ref "IC1") (pin "57") (pinfunction "FB4MC17_57") (pintype "bidirectional"))
      (node (ref "J17") (pin "1") (pinfunction "S_1") (pintype "passive"))
      (node (ref "RN3") (pin "2") (pinfunction "2_2") (pintype "passive"))
    )
    (net (code "55") (name "Net-(IC1A-GCK0)") (class "Default")
      (node (ref "IC1") (pin "15") (pinfunction "GCK0_15") (pintype "input"))
      (node (ref "IC1") (pin "16") (pinfunction "GCK1_16") (pintype "input"))
      (node (ref "IC1") (pin "17") (pinfunction "GCK2_17") (pintype "input"))
      (node (ref "IC2") (pin "31") (pinfunction "OSC2/CLKO/RA6_31") (pintype "bidirectional"))
    )
    (net (code "56") (name "Net-(IC1B-TCK)") (class "Default")
      (node (ref "IC1") (pin "30") (pinfunction "TCK_30") (pintype "input"))
      (node (ref "JP30") (pin "3") (pinfunction "TCK_3") (pintype "passive"))
    )
    (net (code "57") (name "Net-(IC1B-TDI)") (class "Default")
      (node (ref "IC1") (pin "28") (pinfunction "TDI_28") (pintype "input"))
      (node (ref "JP30") (pin "5") (pinfunction "TDI_5") (pintype "passive"))
    )
    (net (code "58") (name "Net-(IC1B-TDO)") (class "Default")
      (node (ref "IC1") (pin "53") (pinfunction "TDO_53") (pintype "output"))
      (node (ref "JP30") (pin "4") (pinfunction "TDO_4") (pintype "passive"))
    )
    (net (code "59") (name "Net-(IC1B-TMS)") (class "Default")
      (node (ref "IC1") (pin "29") (pinfunction "TMS_29") (pintype "input"))
      (node (ref "JP30") (pin "6") (pinfunction "TMS_6") (pintype "passive"))
    )
    (net (code "60") (name "Net-(IC2-MCLR{slash}VPP{slash}RE3)") (class "Default")
      (node (ref "IC2") (pin "18") (pinfunction "MCLR/VPP/RE3_18") (pintype "input"))
      (node (ref "JP31") (pin "1") (pinfunction "VPP/MCLR_1") (pintype "bidirectional"))
    )
    (net (code "61") (name "Net-(IC2-OSC1{slash}DLKI{slash}RA7)") (class "Default")
      (node (ref "IC2") (pin "30") (pinfunction "OSC1/DLKI/RA7_30") (pintype "bidirectional"))
      (node (ref "IC5") (pin "P$3") (pinfunction "OUT_P$3") (pintype "output"))
    )
    (net (code "62") (name "Net-(IC2-RA0{slash}AN0{slash}CVREF)") (class "Default")
      (node (ref "IC2") (pin "19") (pinfunction "RA0/AN0/CVREF_19") (pintype "bidirectional"))
      (node (ref "JP12") (pin "2") (pinfunction "2_2") (pintype "passive"))
      (node (ref "R5") (pin "1") (pinfunction "1_1") (pintype "passive"))
    )
    (net (code "63") (name "Net-(IC2-RA1{slash}AN1)") (class "Default")
      (node (ref "IC2") (pin "20") (pinfunction "RA1/AN1_20") (pintype "bidirectional"))
      (node (ref "JP11") (pin "2") (pinfunction "2_2") (pintype "passive"))
      (node (ref "R4") (pin "1") (pinfunction "1_1") (pintype "passive"))
    )
    (net (code "64") (name "Net-(IC2-RB2{slash}INT2{slash}CANTX)") (class "Default")
      (node (ref "IC2") (pin "10") (pinfunction "RB2/INT2/CANTX_10") (pintype "bidirectional"))
      (node (ref "IC6") (pin "1") (pinfunction "TX_1") (pintype "input"))
    )
    (net (code "65") (name "Net-(IC2-RB3{slash}CANRX)") (class "Default")
      (node (ref "IC2") (pin "11") (pinfunction "RB3/CANRX_11") (pintype "bidirectional"))
      (node (ref "IC6") (pin "4") (pinfunction "RX_4") (pintype "output"))
    )
    (net (code "66") (name "Net-(IC2-RB5KBI1{slash}PGM)") (class "Default")
      (node (ref "IC2") (pin "15") (pinfunction "RB5KBI1/PGM_15") (pintype "bidirectional"))
      (node (ref "JP31") (pin "6") (pinfunction "AUX_6") (pintype "bidirectional"))
    )
    (net (code "67") (name "Net-(IC2-RB6{slash}KBI2{slash}PGC)") (class "Default")
      (node (ref "IC2") (pin "16") (pinfunction "RB6/KBI2/PGC_16") (pintype "bidirectional"))
      (node (ref "JP31") (pin "5") (pinfunction "PGC/ICSPCLK_5") (pintype "bidirectional"))
    )
    (net (code "68") (name "Net-(IC2-RB7{slash}KBI3{slash}PGD)") (class "Default")
      (node (ref "IC2") (pin "17") (pinfunction "RB7/KBI3/PGD_17") (pintype "bidirectional"))
      (node (ref "JP31") (pin "4") (pinfunction "PGD/ICSPDAT_4") (pintype "bidirectional"))
    )
    (net (code "69") (name "Net-(IC3-IN)") (class "Default")
      (node (ref "C1") (pin "2") (pinfunction "2_2") (pintype "passive"))
      (node (ref "C12") (pin "+") (pinfunction "+_+") (pintype "passive"))
      (node (ref "C32") (pin "2") (pinfunction "2_2") (pintype "passive"))
      (node (ref "D1") (pin "C") (pinfunction "C_C") (pintype "passive"))
      (node (ref "D2") (pin "C") (pinfunction "C_C") (pintype "passive"))
      (node (ref "IC3") (pin "1") (pinfunction "IN_1") (pintype "input"))
      (node (ref "IC4") (pin "1") (pinfunction "IN_1") (pintype "input"))
    )
    (net (code "70") (name "Net-(IC6-CANH)") (class "Default")
      (node (ref "IC6") (pin "7") (pinfunction "CANH_7") (pintype "bidirectional"))
      (node (ref "IC7") (pin "1") (pinfunction "A1_1") (pintype "passive"))
      (node (ref "L3") (pin "1") (pinfunction "2_1") (pintype "passive"))
      (node (ref "R6") (pin "1") (pinfunction "1_1") (pintype "passive"))
    )
    (net (code "71") (name "Net-(IC6-CANL)") (class "Default")
      (node (ref "IC6") (pin "6") (pinfunction "CANL_6") (pintype "bidirectional"))
      (node (ref "IC7") (pin "2") (pinfunction "A2_2") (pintype "passive"))
      (node (ref "L3") (pin "2") (pinfunction "1_2") (pintype "passive"))
      (node (ref "R7") (pin "2") (pinfunction "2_2") (pintype "passive"))
    )
    (net (code "72") (name "Net-(IC6-RS)") (class "Default")
      (node (ref "IC6") (pin "8") (pinfunction "RS_8") (pintype "passive"))
      (node (ref "R3") (pin "2") (pinfunction "2_2") (pintype "passive"))
    )
    (net (code "73") (name "Net-(LED1-PadA)") (class "Default")
      (node (ref "LED1") (pin "A") (pinfunction "A_A") (pintype "passive"))
      (node (ref "RN1") (pin "5") (pinfunction "5_5") (pintype "passive"))
    )
    (net (code "74") (name "Net-(LED2-PadA)") (class "Default")
      (node (ref "LED2") (pin "A") (pinfunction "A_A") (pintype "passive"))
      (node (ref "RN1") (pin "9") (pinfunction "9_9") (pintype "passive"))
    )
    (net (code "75") (name "Net-(LED3-PadA)") (class "Default")
      (node (ref "LED3") (pin "A") (pinfunction "A_A") (pintype "passive"))
      (node (ref "RN2") (pin "5") (pinfunction "5_5") (pintype "passive"))
    )
    (net (code "76") (name "Net-(LED4-PadA)") (class "Default")
      (node (ref "LED4") (pin "A") (pinfunction "A_A") (pintype "passive"))
      (node (ref "RN2") (pin "9") (pinfunction "9_9") (pintype "passive"))
    )
    (net (code "77") (name "Net-(LED5-PadA)") (class "Default")
      (node (ref "LED5") (pin "A") (pinfunction "A_A") (pintype "passive"))
      (node (ref "RN3") (pin "5") (pinfunction "5_5") (pintype "passive"))
    )
    (net (code "78") (name "Net-(LED6-PadA)") (class "Default")
      (node (ref "LED6") (pin "A") (pinfunction "A_A") (pintype "passive"))
      (node (ref "RN3") (pin "9") (pinfunction "9_9") (pintype "passive"))
    )
    (net (code "79") (name "Net-(LED7-PadA)") (class "Default")
      (node (ref "LED7") (pin "A") (pinfunction "A_A") (pintype "passive"))
      (node (ref "RN4") (pin "5") (pinfunction "5_5") (pintype "passive"))
    )
    (net (code "80") (name "Net-(LED8-PadA)") (class "Default")
      (node (ref "LED8") (pin "A") (pinfunction "A_A") (pintype "passive"))
      (node (ref "RN4") (pin "9") (pinfunction "9_9") (pintype "passive"))
    )
    (net (code "81") (name "Net-(OK1-A)") (class "Default")
      (node (ref "OK1") (pin "1") (pinfunction "A_1") (pintype "passive"))
      (node (ref "R2") (pin "1") (pinfunction "1_1") (pintype "passive"))
    )
    (net (code "82") (name "Net-(OK1-COL)") (class "Default")
      (node (ref "JP10") (pin "4") (pinfunction "4_4") (pintype "passive"))
      (node (ref "OK1") (pin "4") (pinfunction "COL_4") (pintype "passive"))
    )
    (net (code "83") (name "Net-(OK1-EMIT)") (class "Default")
      (node (ref "JP10") (pin "3") (pinfunction "3_3") (pintype "passive"))
      (node (ref "OK1") (pin "3") (pinfunction "EMIT_3") (pintype "passive"))
    )
    (net (code "84") (name "Net-(OK2-A)") (class "Default")
      (node (ref "OK2") (pin "1") (pinfunction "A_1") (pintype "passive"))
      (node (ref "R1") (pin "1") (pinfunction "1_1") (pintype "passive"))
    )
    (net (code "85") (name "Net-(OK2-COL)") (class "Default")
      (node (ref "JP10") (pin "2") (pinfunction "2_2") (pintype "passive"))
      (node (ref "OK2") (pin "4") (pinfunction "COL_4") (pintype "passive"))
    )
    (net (code "86") (name "Net-(OK2-EMIT)") (class "Default")
      (node (ref "JP10") (pin "1") (pinfunction "1_1") (pintype "passive"))
      (node (ref "OK2") (pin "3") (pinfunction "EMIT_3") (pintype "passive"))
    )
    (net (code "87") (name "Net-(PWR1A-S)") (class "Default")
      (node (ref "F1") (pin "2") (pinfunction "2_2") (pintype "passive"))
      (node (ref "PWR1") (pin "1") (pinfunction "S_1") (pintype "passive"))
      (node (ref "PWR2") (pin "1") (pinfunction "S_1") (pintype "passive"))
    )
    (net (code "88") (name "unconnected-(IC2-NC-Pad13)") (class "Default")
      (node (ref "IC2") (pin "13") (pinfunction "NC_13") (pintype "no_connect"))
    )
    (net (code "89") (name "unconnected-(IC2-RA2{slash}AN2{slash}VREF--Pad21)") (class "Default")
      (node (ref "IC2") (pin "21") (pinfunction "RA2/AN2/VREF-_21") (pintype "bidirectional"))
    )
    (net (code "90") (name "unconnected-(IC2-RA3{slash}AN3{slash}VREF+-Pad22)") (class "Default")
      (node (ref "IC2") (pin "22") (pinfunction "RA3/AN3/VREF+_22") (pintype "bidirectional"))
    )
    (net (code "91") (name "unconnected-(IC2-RA4{slash}T0CKI-Pad23)") (class "Default")
      (node (ref "IC2") (pin "23") (pinfunction "RA4/T0CKI_23") (pintype "bidirectional"))
    )
    (net (code "92") (name "unconnected-(IC2-RA5{slash}AN4{slash}SSI{slash}HLVDIN-Pad24)") (class "Default")
      (node (ref "IC2") (pin "24") (pinfunction "RA5/AN4/SSI/HLVDIN_24") (pintype "bidirectional"))
    )
    (net (code "93") (name "unconnected-(IC2-RB4{slash}KBIO{slash}AN9-Pad14)") (class "Default")
      (node (ref "IC2") (pin "14") (pinfunction "RB4/KBIO/AN9_14") (pintype "bidirectional"))
    )
    (net (code "94") (name "unconnected-(IC2-RC0{slash}T1OSO{slash}T13CKI-Pad32)") (class "Default")
      (node (ref "IC2") (pin "32") (pinfunction "RC0/T1OSO/T13CKI_32") (pintype "bidirectional"))
    )
    (net (code "95") (name "unconnected-(IC2-RC1{slash}T1OSI-Pad35)") (class "Default")
      (node (ref "IC2") (pin "35") (pinfunction "RC1/T1OSI_35") (pintype "bidirectional"))
    )
    (net (code "96") (name "unconnected-(IC2-RC2{slash}CCP1-Pad36)") (class "Default")
      (node (ref "IC2") (pin "36") (pinfunction "RC2/CCP1_36") (pintype "bidirectional"))
    )
    (net (code "97") (name "unconnected-(IC2-RC3{slash}SCK{slash}SCL-Pad37)") (class "Default")
      (node (ref "IC2") (pin "37") (pinfunction "RC3/SCK/SCL_37") (pintype "bidirectional"))
    )
    (net (code "98") (name "unconnected-(IC2-RC4{slash}SDI{slash}SDA-Pad42)") (class "Default")
      (node (ref "IC2") (pin "42") (pinfunction "RC4/SDI/SDA_42") (pintype "bidirectional"))
    )
    (net (code "99") (name "unconnected-(IC2-RC5{slash}SDO-Pad43)") (class "Default")
      (node (ref "IC2") (pin "43") (pinfunction "RC5/SDO_43") (pintype "bidirectional"))
    )
    (net (code "100") (name "unconnected-(IC2-RE0{slash}RD{slash}AN5-Pad25)") (class "Default")
      (node (ref "IC2") (pin "25") (pinfunction "RE0/RD/AN5_25") (pintype "bidirectional"))
    )
    (net (code "101") (name "unconnected-(IC2-RE1{slash}WR{slash}AN6{slash}C1OUT-Pad26)") (class "Default")
      (node (ref "IC2") (pin "26") (pinfunction "RE1/WR/AN6/C1OUT_26") (pintype "bidirectional"))
    )
    (net (code "102") (name "unconnected-(IC2-RE2{slash}CS{slash}AN7{slash}C2OUT-Pad27)") (class "Default")
      (node (ref "IC2") (pin "27") (pinfunction "RE2/CS/AN7/C2OUT_27") (pintype "bidirectional"))
    )
    (net (code "103") (name "unconnected-(IC5-TS-PadP$1)") (class "Default")
      (node (ref "IC5") (pin "P$1") (pinfunction "TS_P$1") (pintype "passive"))
    )
    (net (code "104") (name "unconnected-(IC6-VREF-Pad5)") (class "Default")
      (node (ref "IC6") (pin "5") (pinfunction "VREF_5") (pintype "output"))
    )
  )
)
